# SCH_d_00_e_00.net
KiCad netlist of a schematic drawn in EasyEDA
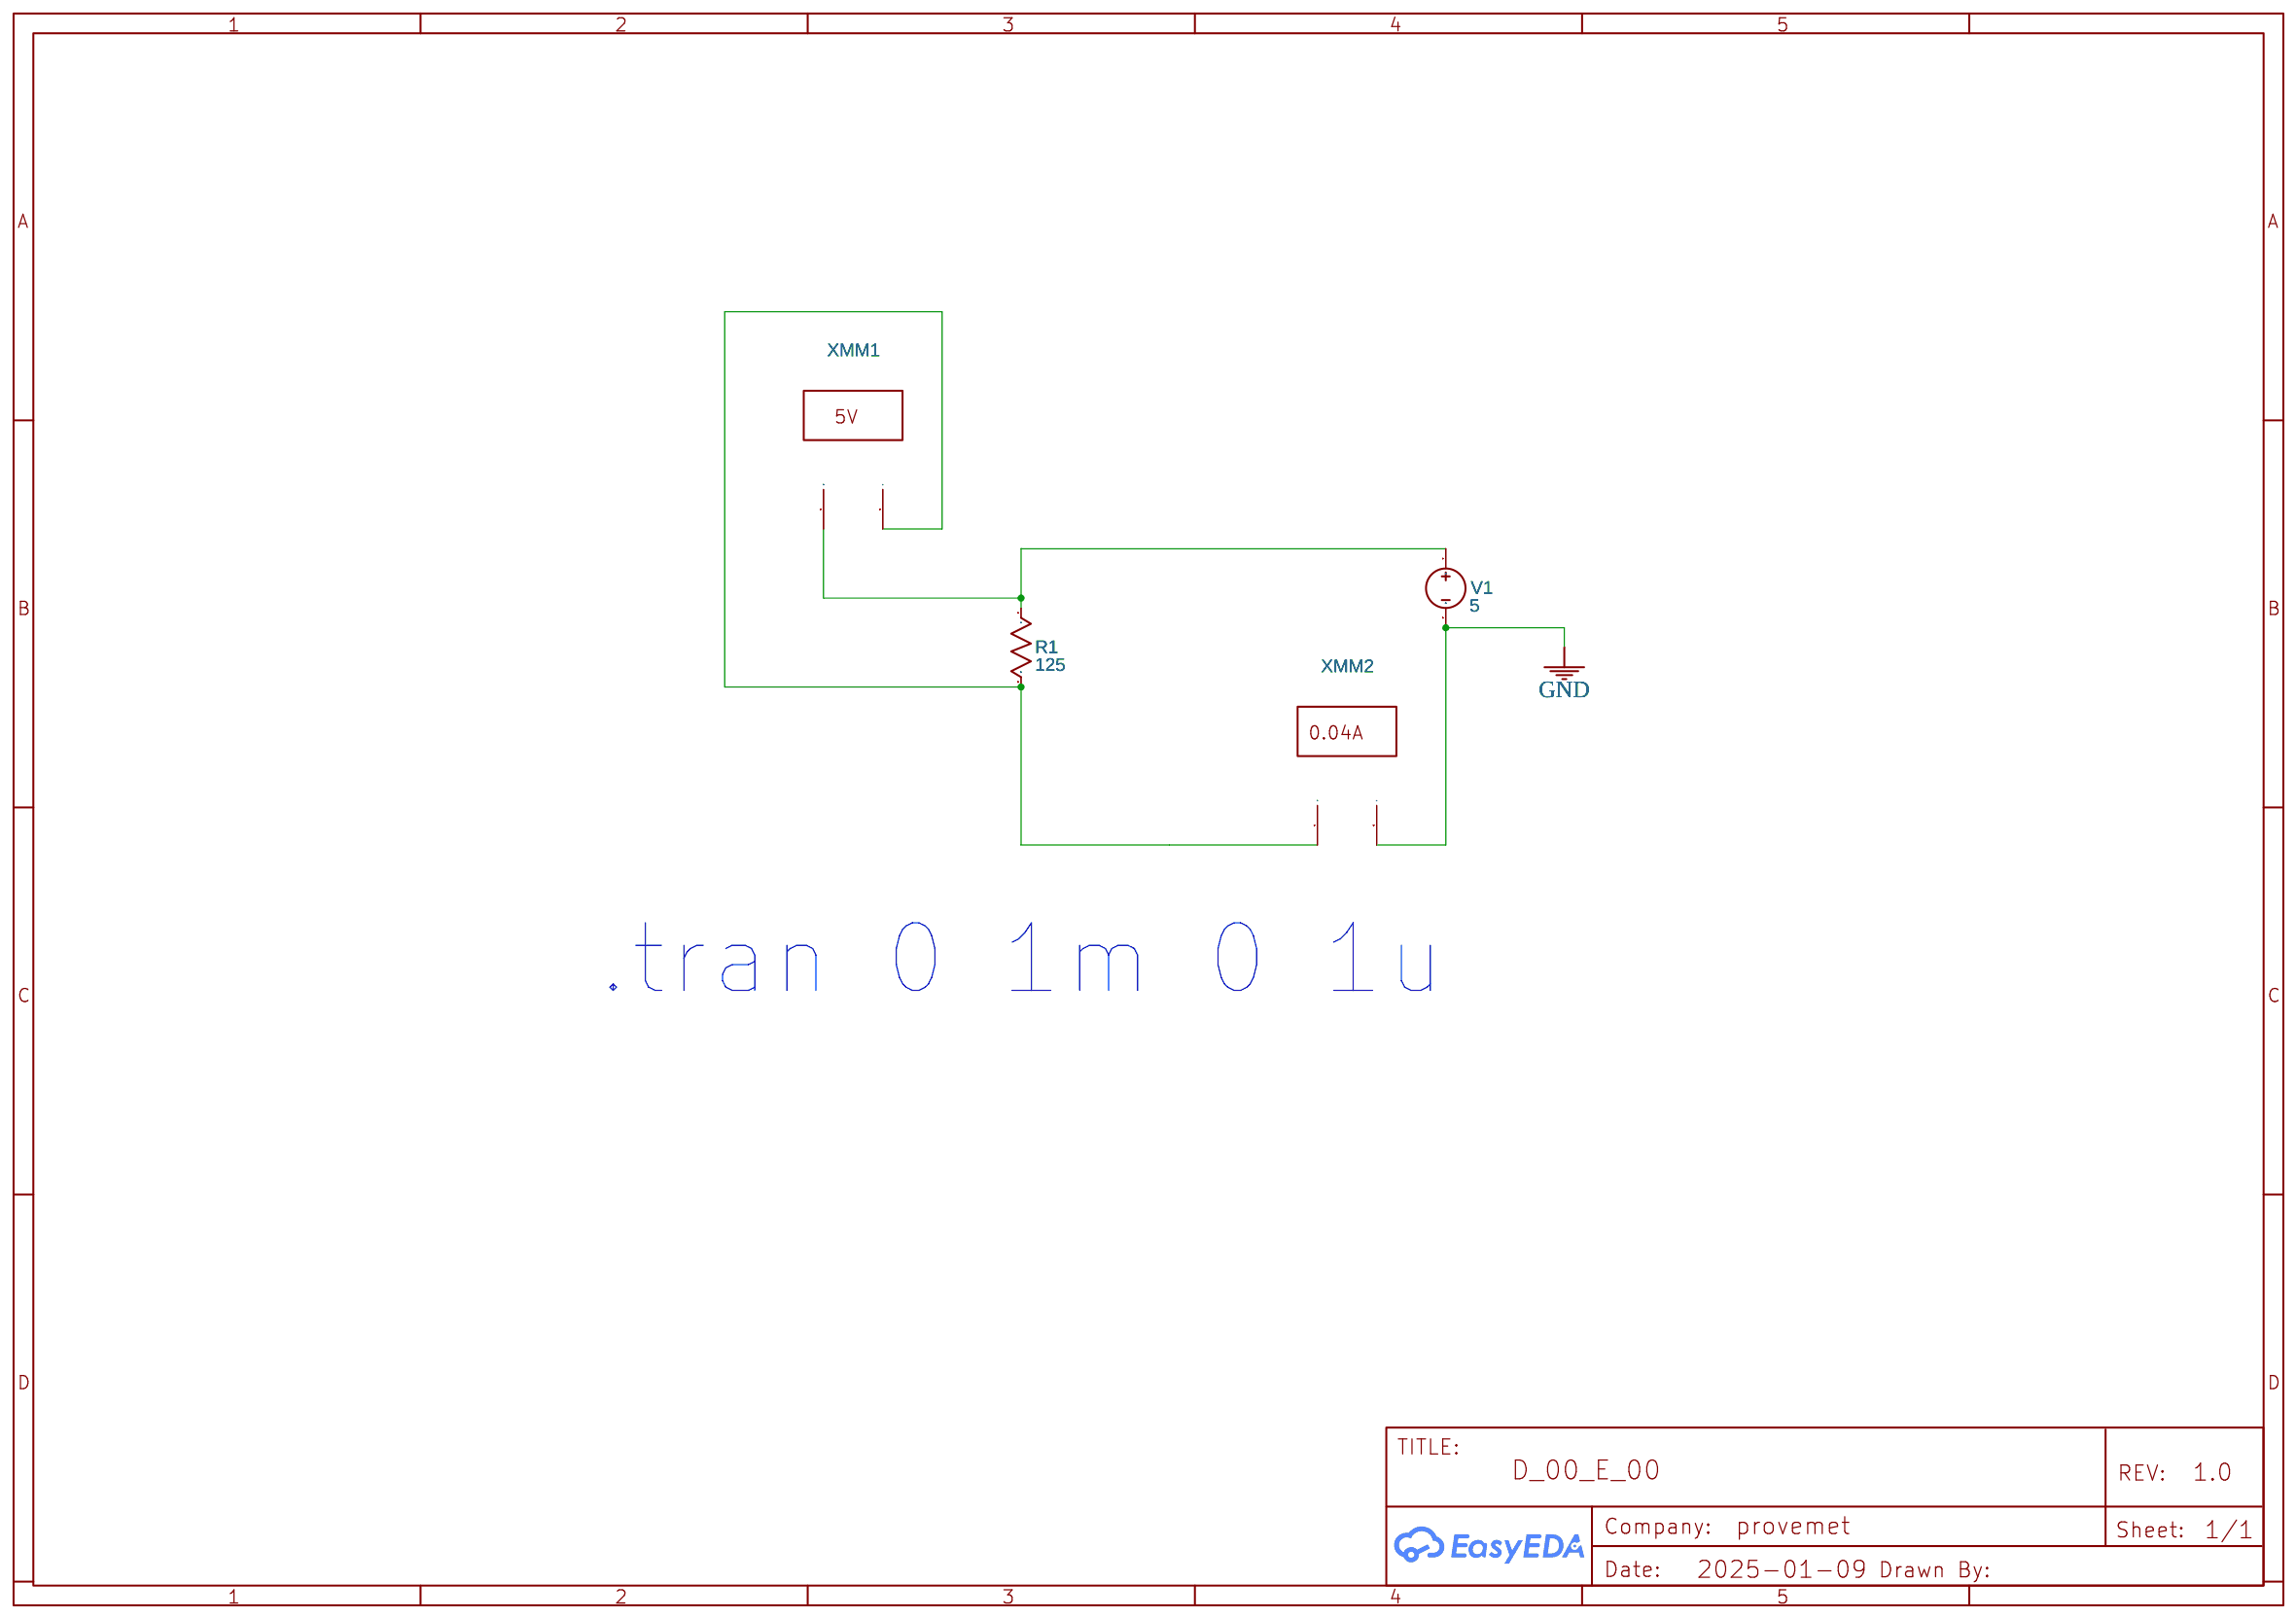
[diagram p0: schematic sheet]

(export (version "E")
  (design (tool "Eeschema 10.0.6"))
  (components
    (comp (ref "R1") (value "125") (libsource (lib "") (part "Resistor_US")))
    (comp (ref "V1") (value "5") (libsource (lib "") (part "VDC")))
    (comp (ref "XMM1") (value "Multimeter") (libsource (lib "") (part "MULTIMETER_1")))
    (comp (ref "XMM2") (value "Multimeter") (libsource (lib "") (part "MULTIMETER")))
  )
  (nets
    (net (code "1") (name "GND") (class "Default")
      (node (ref "V1") (pin "2") (pinfunction "2_2") (pintype "unspecified"))
      (node (ref "XMM2") (pin "2") (pinfunction "I_2") (pintype "unspecified"))
    )
    (net (code "2") (name "Net-(XMM1-+)") (class "Default")
      (node (ref "R1") (pin "1") (pinfunction "1_1") (pintype "unspecified"))
      (node (ref "V1") (pin "1") (pinfunction "1_1") (pintype "unspecified"))
      (node (ref "XMM1") (pin "1") (pinfunction "+_1") (pintype "unspecified"))
    )
    (net (code "3") (name "Net-(XMM1-I)") (class "Default")
      (node (ref "R1") (pin "2") (pinfunction "2_2") (pintype "unspecified"))
      (node (ref "XMM1") (pin "2") (pinfunction "I_2") (pintype "unspecified"))
      (node (ref "XMM2") (pin "1") (pinfunction "+_1") (pintype "unspecified"))
    )
  )
)
